# Arduino__Connectors.net
KiCad netlist of a schematic drawn in Altium Designer
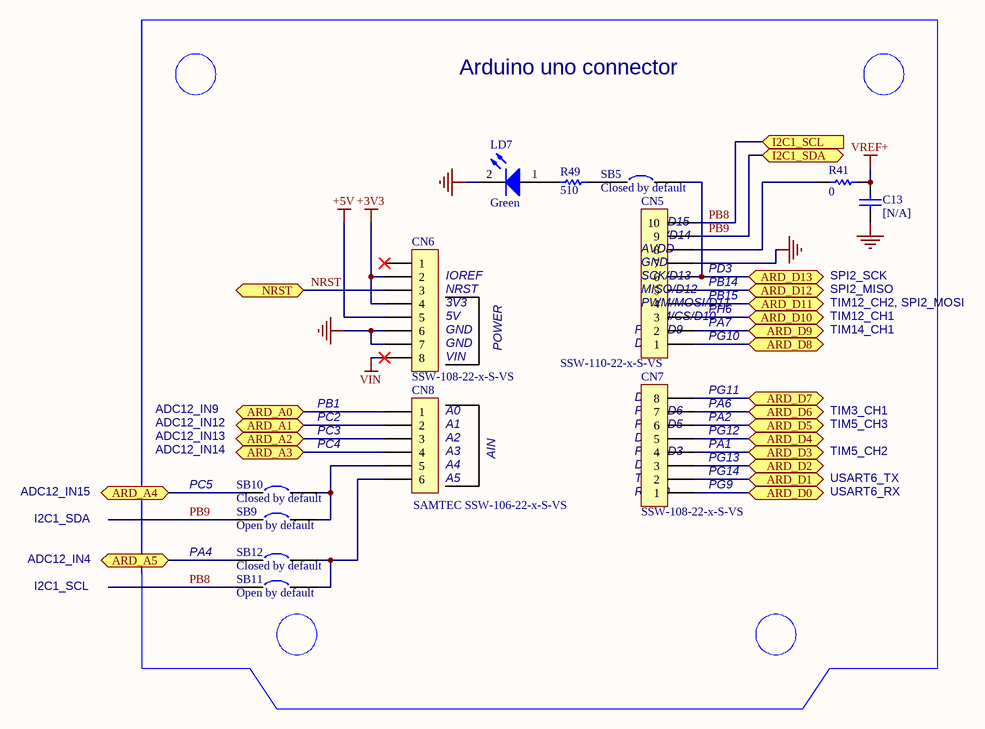
[diagram p0: Arduino_ Connectors.SchDoc]

(export (version "E")
  (design (tool "Eeschema 10.0.6"))
  (components
    (comp (ref "C13")
      (value "[N/A]")
      (footprint "0603C")
      (description "Capacitor")
      (fields (field (name "PUBLISHER") "Altium Limited"))
      (libsource (lib "Miscellaneous Devices") (part "Cap"))
    )
    (comp (ref "CN5")
      (value "SSW-110-22-x-S-VS")
      (footprint "SSW-110-22-X-S-VS")
      (description "Header, 10-Pin, Single row,female")
      (fields (field (name "PUBLISHER") "Altium Limited"))
      (libsource (lib "Nucleo_64") (part "Header 10X1_Female"))
    )
    (comp (ref "CN6")
      (value "SSW-108-22-x-S-VS")
      (footprint "SSW-108-22-X-S-VS")
      (description "Header, 8-Pin, Single row,female")
      (fields (field (name "PUBLISHER") "Altium Limited"))
      (libsource (lib "Nucleo_64") (part "Header 8X1_Female"))
    )
    (comp (ref "CN7")
      (value "SSW-108-22-x-S-VS")
      (footprint "SSW-108-22-X-S-VS")
      (description "Header, 8-Pin, Single row,female")
      (fields (field (name "PUBLISHER") "Altium Limited"))
      (libsource (lib "") (part "Header 8X1_Female_1"))
    )
    (comp (ref "CN8")
      (value "SAMTEC SSW-106-22-x-S-VS")
      (footprint "SSW-106-22-X-S-VS")
      (description "Header, 6-Pin, Single row,female SMD")
      (fields (field (name "PUBLISHER") "Altium Limited"))
      (libsource (lib "Nucleo_64") (part "Header 6X1_Female"))
    )
    (comp (ref "LD7")
      (value "Green")
      (footprint "0603D")
      (description "Typical RED, GREEN, YELLOW, AMBER GaAs LED")
      (fields (field (name "PUBLISHER") "Altium Limited"))
      (libsource (lib "Miscellaneous Devices") (part "LED2"))
    )
    (comp (ref "R41")
      (value "0")
      (footprint "0603R")
      (description "Resistor")
      (fields (field (name "PUBLISHER") "Altium Limited"))
      (libsource (lib "Miscellaneous Devices") (part "Res1"))
    )
    (comp (ref "R49")
      (value "510")
      (footprint "0603R")
      (description "Resistor")
      (fields (field (name "PUBLISHER") "Altium Limited"))
      (libsource (lib "Miscellaneous Devices") (part "Res1"))
    )
    (comp (ref "SB5")
      (value "Closed by default")
      (footprint "SB_0603")
      (description "Circuit Breaker")
      (fields (field (name "PUBLISHER") "Altium Limited"))
      (libsource (lib "Miscellaneous Devices") (part "Circuit Breaker"))
    )
    (comp (ref "SB9")
      (value "Open by default")
      (footprint "SB_0603")
      (description "Circuit Breaker")
      (fields (field (name "PUBLISHER") "Altium Limited"))
      (libsource (lib "Miscellaneous Devices") (part "Circuit Breaker"))
    )
    (comp (ref "SB10")
      (value "Closed by default")
      (footprint "SB_0603")
      (description "Circuit Breaker")
      (fields (field (name "PUBLISHER") "Altium Limited"))
      (libsource (lib "Miscellaneous Devices") (part "Circuit Breaker"))
    )
    (comp (ref "SB11")
      (value "Open by default")
      (footprint "SB_0603")
      (description "Circuit Breaker")
      (fields (field (name "PUBLISHER") "Altium Limited"))
      (libsource (lib "Miscellaneous Devices") (part "Circuit Breaker"))
    )
    (comp (ref "SB12")
      (value "Closed by default")
      (footprint "SB_0603")
      (description "Circuit Breaker")
      (fields (field (name "PUBLISHER") "Altium Limited"))
      (libsource (lib "Miscellaneous Devices") (part "Circuit Breaker"))
    )
  )
  (nets
    (net (code "1") (name "+3V3") (class "Default")
      (node (ref "CN6") (pin "2") (pinfunction "2_2") (pintype "passive"))
      (node (ref "CN6") (pin "4") (pinfunction "4_4") (pintype "passive"))
    )
    (net (code "2") (name "+5V") (class "Default")
      (node (ref "CN6") (pin "5") (pinfunction "5_5") (pintype "passive"))
    )
    (net (code "3") (name "/ARD_A0") (class "Default")
      (node (ref "CN8") (pin "1") (pinfunction "1_1") (pintype "passive"))
    )
    (net (code "4") (name "/ARD_A1") (class "Default")
      (node (ref "CN8") (pin "2") (pinfunction "2_2") (pintype "passive"))
    )
    (net (code "5") (name "/ARD_A2") (class "Default")
      (node (ref "CN8") (pin "3") (pinfunction "3_3") (pintype "passive"))
    )
    (net (code "6") (name "/ARD_A3") (class "Default")
      (node (ref "CN8") (pin "4") (pinfunction "4_4") (pintype "passive"))
    )
    (net (code "7") (name "/ARD_A4") (class "Default")
      (node (ref "SB10") (pin "1") (pinfunction "1_1") (pintype "passive"))
    )
    (net (code "8") (name "/ARD_A5") (class "Default")
      (node (ref "SB12") (pin "1") (pinfunction "1_1") (pintype "passive"))
    )
    (net (code "9") (name "/ARD_D0") (class "Default")
      (node (ref "CN7") (pin "1") (pinfunction "1_1") (pintype "passive"))
    )
    (net (code "10") (name "/ARD_D1") (class "Default")
      (node (ref "CN7") (pin "2") (pinfunction "2_2") (pintype "passive"))
    )
    (net (code "11") (name "/ARD_D2") (class "Default")
      (node (ref "CN7") (pin "3") (pinfunction "3_3") (pintype "passive"))
    )
    (net (code "12") (name "/ARD_D3") (class "Default")
      (node (ref "CN7") (pin "4") (pinfunction "4_4") (pintype "passive"))
    )
    (net (code "13") (name "/ARD_D4") (class "Default")
      (node (ref "CN7") (pin "5") (pinfunction "5_5") (pintype "passive"))
    )
    (net (code "14") (name "/ARD_D5") (class "Default")
      (node (ref "CN7") (pin "6") (pinfunction "6_6") (pintype "passive"))
    )
    (net (code "15") (name "/ARD_D6") (class "Default")
      (node (ref "CN7") (pin "7") (pinfunction "7_7") (pintype "passive"))
    )
    (net (code "16") (name "/ARD_D7") (class "Default")
      (node (ref "CN7") (pin "8") (pinfunction "8_8") (pintype "passive"))
    )
    (net (code "17") (name "/ARD_D8") (class "Default")
      (node (ref "CN5") (pin "1") (pinfunction "1_1") (pintype "passive"))
    )
    (net (code "18") (name "/ARD_D9") (class "Default")
      (node (ref "CN5") (pin "2") (pinfunction "2_2") (pintype "passive"))
    )
    (net (code "19") (name "/ARD_D10") (class "Default")
      (node (ref "CN5") (pin "3") (pinfunction "3_3") (pintype "passive"))
    )
    (net (code "20") (name "/ARD_D11") (class "Default")
      (node (ref "CN5") (pin "4") (pinfunction "4_4") (pintype "passive"))
    )
    (net (code "21") (name "/ARD_D12") (class "Default")
      (node (ref "CN5") (pin "5") (pinfunction "5_5") (pintype "passive"))
    )
    (net (code "22") (name "/ARD_D13") (class "Default")
      (node (ref "CN5") (pin "6") (pinfunction "6_6") (pintype "passive"))
      (node (ref "SB5") (pin "2") (pinfunction "2_2") (pintype "passive"))
    )
    (net (code "23") (name "/NRST") (class "Default")
      (node (ref "CN6") (pin "3") (pinfunction "3_3") (pintype "passive"))
    )
    (net (code "24") (name "/PB8") (class "Default")
      (node (ref "CN5") (pin "10") (pinfunction "10_10") (pintype "passive"))
      (node (ref "SB11") (pin "1") (pinfunction "1_1") (pintype "passive"))
    )
    (net (code "25") (name "/PB9") (class "Default")
      (node (ref "CN5") (pin "9") (pinfunction "9_9") (pintype "passive"))
      (node (ref "SB9") (pin "1") (pinfunction "1_1") (pintype "passive"))
    )
    (net (code "26") (name "GND") (class "Default")
      (node (ref "C13") (pin "1") (pinfunction "1_1") (pintype "passive"))
      (node (ref "CN5") (pin "7") (pinfunction "7_7") (pintype "passive"))
      (node (ref "CN6") (pin "6") (pinfunction "6_6") (pintype "passive"))
      (node (ref "CN6") (pin "7") (pinfunction "7_7") (pintype "passive"))
      (node (ref "LD7") (pin "2") (pinfunction "K_2") (pintype "passive"))
    )
    (net (code "27") (name "Net-(CN5-Pad8)") (class "Default")
      (node (ref "CN5") (pin "8") (pinfunction "8_8") (pintype "passive"))
      (node (ref "R41") (pin "2") (pinfunction "2_2") (pintype "passive"))
    )
    (net (code "28") (name "Net-(CN8-Pad5)") (class "Default")
      (node (ref "CN8") (pin "5") (pinfunction "5_5") (pintype "passive"))
      (node (ref "SB10") (pin "2") (pinfunction "2_2") (pintype "passive"))
      (node (ref "SB9") (pin "2") (pinfunction "2_2") (pintype "passive"))
    )
    (net (code "29") (name "Net-(CN8-Pad6)") (class "Default")
      (node (ref "CN8") (pin "6") (pinfunction "6_6") (pintype "passive"))
      (node (ref "SB11") (pin "2") (pinfunction "2_2") (pintype "passive"))
      (node (ref "SB12") (pin "2") (pinfunction "2_2") (pintype "passive"))
    )
    (net (code "30") (name "Net-(LD7-A)") (class "Default")
      (node (ref "LD7") (pin "1") (pinfunction "A_1") (pintype "passive"))
      (node (ref "R49") (pin "2") (pinfunction "2_2") (pintype "passive"))
    )
    (net (code "31") (name "Net-(R49-Pad1)") (class "Default")
      (node (ref "R49") (pin "1") (pinfunction "1_1") (pintype "passive"))
      (node (ref "SB5") (pin "1") (pinfunction "1_1") (pintype "passive"))
    )
    (net (code "32") (name "VIN") (class "Default")
      (node (ref "CN6") (pin "8") (pinfunction "8_8") (pintype "passive"))
    )
    (net (code "33") (name "VREF+") (class "Default")
      (node (ref "C13") (pin "2") (pinfunction "2_2") (pintype "passive"))
      (node (ref "R41") (pin "1") (pinfunction "1_1") (pintype "passive"))
    )
    (net (code "34") (name "unconnected-(CN6-Pad1)") (class "Default")
      (node (ref "CN6") (pin "1") (pinfunction "1_1") (pintype "passive+no_connect"))
    )
  )
)
